# E77T.net
KiCad netlist of a schematic drawn in Altium Designer
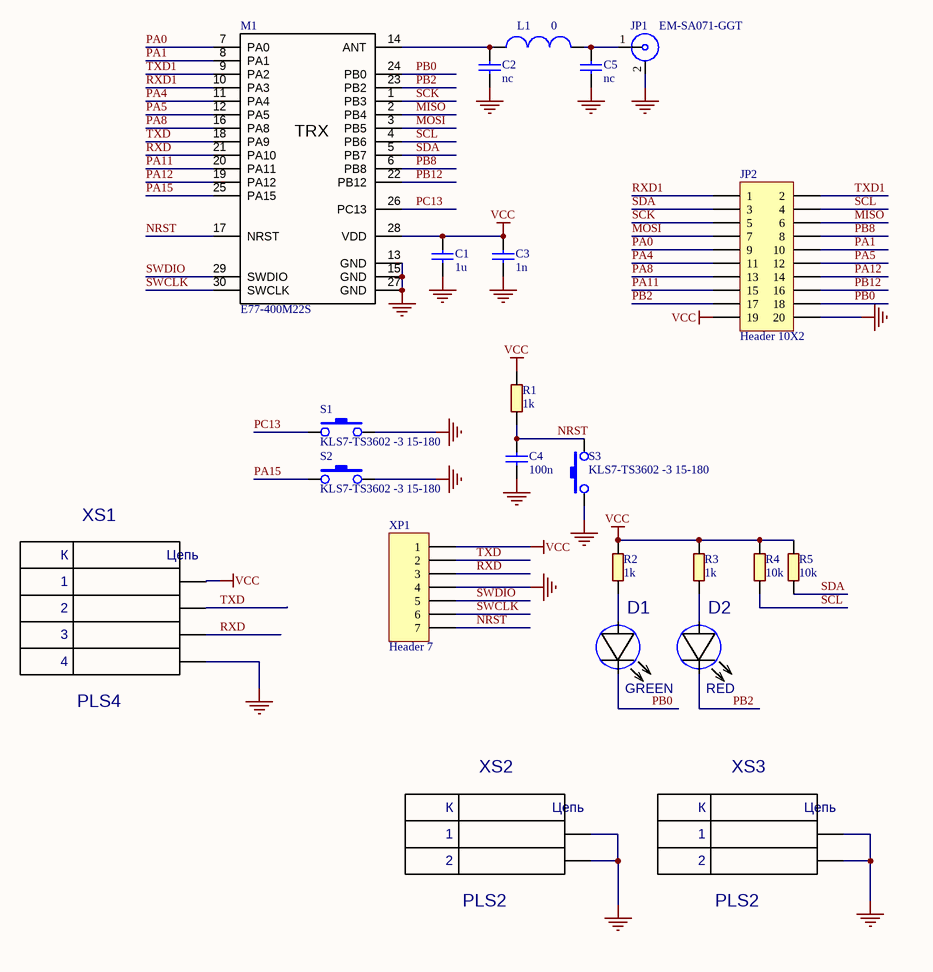
[diagram p0: E77T.SchDoc]

(export (version "E")
  (design (tool "Eeschema 10.0.6"))
  (components
    (comp (ref "C1")
      (value "1u")
      (footprint "C-0603")
      (fields (field (name "VOLTAGE") "50V"))
      (libsource (lib "Passive") (part "CAPN"))
    )
    (comp (ref "C2")
      (value "nc")
      (footprint "C-0603")
      (fields (field (name "VOLTAGE") "50V"))
      (libsource (lib "Passive") (part "CAPN"))
    )
    (comp (ref "C3")
      (value "1n")
      (footprint "C-0603")
      (fields (field (name "VOLTAGE") "50V"))
      (libsource (lib "Passive") (part "CAPN"))
    )
    (comp (ref "C4")
      (value "100n")
      (footprint "C-0603")
      (fields (field (name "VOLTAGE") "50V"))
      (libsource (lib "Passive") (part "CAPN"))
    )
    (comp (ref "C5")
      (value "nc")
      (footprint "C-0603")
      (fields (field (name "VOLTAGE") "50V"))
      (libsource (lib "Passive") (part "CAPN"))
    )
    (comp (ref "D1")
      (value "GREEN")
      (footprint "LED_3mm_RED")
      (fields (field (name "Comment") "LED3mm"))
      (libsource (lib "E2002") (part "LED3mm"))
    )
    (comp (ref "D2")
      (value "RED")
      (footprint "LED_3mm_RED")
      (fields (field (name "Comment") "LED3mm"))
      (libsource (lib "E2002") (part "LED3mm"))
    )
    (comp (ref "JP1")
      (value "EM-SA071-GGT")
      (footprint "SMA_F_EDGE")
      (description "SMA Female R/A PCB Mount")
      (libsource (lib "Connectors") (part "SMA"))
    )
    (comp (ref "JP2")
      (value "Header 10X2")
      (footprint "HDR2X10")
      (description "Header, 10-Pin, Dual row")
      (fields (field (name "PUBLISHER") "Altium Limited"))
      (libsource (lib "Miscellaneous Connectors") (part "Header 10X2"))
    )
    (comp (ref "L1") (value "0") (footprint "L-0603") (libsource (lib "Passive") (part "L")))
    (comp (ref "M1")
      (value "E77-400M22S")
      (footprint "E77XX-M22")
      (libsource (lib "zucker") (part "E77-400M22S"))
    )
    (comp (ref "R1") (value "1k") (footprint "R-0603") (libsource (lib "Passive") (part "RES")))
    (comp (ref "R2") (value "1k") (footprint "R-0603") (libsource (lib "Passive") (part "RES")))
    (comp (ref "R3") (value "1k") (footprint "R-0603") (libsource (lib "Passive") (part "RES")))
    (comp (ref "R4") (value "10k") (footprint "R-0603") (libsource (lib "Passive") (part "RES")))
    (comp (ref "R5") (value "10k") (footprint "R-0603") (libsource (lib "Passive") (part "RES")))
    (comp (ref "S1")
      (value "KLS7-TS3602 -3 15-180")
      (footprint "BUTT_MIN")
      (libsource (lib "Switches") (part "SW-1"))
    )
    (comp (ref "S2")
      (value "KLS7-TS3602 -3 15-180")
      (footprint "BUTT_MIN")
      (libsource (lib "Switches") (part "SW-1"))
    )
    (comp (ref "S3")
      (value "KLS7-TS3602 -3 15-180")
      (footprint "BUTT_MIN")
      (libsource (lib "Switches") (part "SW-1"))
    )
    (comp (ref "XP1")
      (value "Header 7")
      (footprint "PLS1-7R")
      (description "Header, 7-Pin")
      (fields (field (name "PUBLISHER") "Altium Limited"))
      (libsource (lib "Miscellaneous Connectors") (part "Header 7"))
    )
    (comp (ref "XS1") (value "PLS4") (footprint "PLS4 - 3D") (libsource (lib "E2002") (part "PLS4")))
    (comp (ref "XS2") (value "PLS2") (footprint "PLS2 - 3D") (libsource (lib "E2002") (part "PLS2")))
    (comp (ref "XS3") (value "PLS2") (footprint "PLS2 - 3D") (libsource (lib "E2002") (part "PLS2")))
  )
  (nets
    (net (code "1") (name "/MISO") (class "Default")
      (node (ref "JP2") (pin "6") (pinfunction "6_6") (pintype "passive"))
      (node (ref "M1") (pin "2") (pinfunction "PB4_2") (pintype "passive"))
    )
    (net (code "2") (name "/MOSI") (class "Default")
      (node (ref "JP2") (pin "7") (pinfunction "7_7") (pintype "passive"))
      (node (ref "M1") (pin "3") (pinfunction "PB5_3") (pintype "passive"))
    )
    (net (code "3") (name "/NRST") (class "Default")
      (node (ref "C4") (pin "1") (pinfunction "1_1") (pintype "passive"))
      (node (ref "M1") (pin "17") (pinfunction "NRST_17") (pintype "passive"))
      (node (ref "R1") (pin "1") (pinfunction "1_1") (pintype "passive"))
      (node (ref "S3") (pin "2") (pinfunction "2_2") (pintype "passive"))
      (node (ref "XP1") (pin "7") (pinfunction "7_7") (pintype "passive"))
    )
    (net (code "4") (name "/PA0") (class "Default")
      (node (ref "JP2") (pin "9") (pinfunction "9_9") (pintype "passive"))
      (node (ref "M1") (pin "7") (pinfunction "PA0_7") (pintype "passive"))
    )
    (net (code "5") (name "/PA1") (class "Default")
      (node (ref "JP2") (pin "10") (pinfunction "10_10") (pintype "passive"))
      (node (ref "M1") (pin "8") (pinfunction "PA1_8") (pintype "passive"))
    )
    (net (code "6") (name "/PA4") (class "Default")
      (node (ref "JP2") (pin "11") (pinfunction "11_11") (pintype "passive"))
      (node (ref "M1") (pin "11") (pinfunction "PA4_11") (pintype "passive"))
    )
    (net (code "7") (name "/PA5") (class "Default")
      (node (ref "JP2") (pin "12") (pinfunction "12_12") (pintype "passive"))
      (node (ref "M1") (pin "12") (pinfunction "PA5_12") (pintype "passive"))
    )
    (net (code "8") (name "/PA8") (class "Default")
      (node (ref "JP2") (pin "13") (pinfunction "13_13") (pintype "passive"))
      (node (ref "M1") (pin "16") (pinfunction "PA8_16") (pintype "passive"))
    )
    (net (code "9") (name "/PA11") (class "Default")
      (node (ref "JP2") (pin "15") (pinfunction "15_15") (pintype "passive"))
      (node (ref "M1") (pin "20") (pinfunction "PA11_20") (pintype "passive"))
    )
    (net (code "10") (name "/PA12") (class "Default")
      (node (ref "JP2") (pin "14") (pinfunction "14_14") (pintype "passive"))
      (node (ref "M1") (pin "19") (pinfunction "PA12_19") (pintype "passive"))
    )
    (net (code "11") (name "/PA15") (class "Default")
      (node (ref "M1") (pin "25") (pinfunction "PA15_25") (pintype "passive"))
      (node (ref "S2") (pin "1") (pinfunction "1_1") (pintype "passive"))
    )
    (net (code "12") (name "/PB0") (class "Default")
      (node (ref "D1") (pin "2") (pinfunction "2_2") (pintype "passive"))
      (node (ref "JP2") (pin "18") (pinfunction "18_18") (pintype "passive"))
      (node (ref "M1") (pin "24") (pinfunction "PB0_24") (pintype "passive"))
    )
    (net (code "13") (name "/PB2") (class "Default")
      (node (ref "D2") (pin "2") (pinfunction "2_2") (pintype "passive"))
      (node (ref "JP2") (pin "17") (pinfunction "17_17") (pintype "passive"))
      (node (ref "M1") (pin "23") (pinfunction "PB2_23") (pintype "passive"))
    )
    (net (code "14") (name "/PB8") (class "Default")
      (node (ref "JP2") (pin "8") (pinfunction "8_8") (pintype "passive"))
      (node (ref "M1") (pin "6") (pinfunction "PB8_6") (pintype "passive"))
    )
    (net (code "15") (name "/PB12") (class "Default")
      (node (ref "JP2") (pin "16") (pinfunction "16_16") (pintype "passive"))
      (node (ref "M1") (pin "22") (pinfunction "PB12_22") (pintype "passive"))
    )
    (net (code "16") (name "/PC13") (class "Default")
      (node (ref "M1") (pin "26") (pinfunction "PC13_26") (pintype "passive"))
      (node (ref "S1") (pin "1") (pinfunction "1_1") (pintype "passive"))
    )
    (net (code "17") (name "/RXD") (class "Default")
      (node (ref "M1") (pin "21") (pinfunction "PA10_21") (pintype "passive"))
      (node (ref "XP1") (pin "3") (pinfunction "3_3") (pintype "passive"))
      (node (ref "XS1") (pin "3") (pinfunction "3_3") (pintype "passive"))
    )
    (net (code "18") (name "/RXD1") (class "Default")
      (node (ref "JP2") (pin "1") (pinfunction "1_1") (pintype "passive"))
      (node (ref "M1") (pin "10") (pinfunction "PA3_10") (pintype "passive"))
    )
    (net (code "19") (name "/SCK") (class "Default")
      (node (ref "JP2") (pin "5") (pinfunction "5_5") (pintype "passive"))
      (node (ref "M1") (pin "1") (pinfunction "PB3_1") (pintype "passive"))
    )
    (net (code "20") (name "/SCL") (class "Default")
      (node (ref "JP2") (pin "4") (pinfunction "4_4") (pintype "passive"))
      (node (ref "M1") (pin "4") (pinfunction "PB6_4") (pintype "passive"))
      (node (ref "R4") (pin "1") (pinfunction "1_1") (pintype "passive"))
    )
    (net (code "21") (name "/SDA") (class "Default")
      (node (ref "JP2") (pin "3") (pinfunction "3_3") (pintype "passive"))
      (node (ref "M1") (pin "5") (pinfunction "PB7_5") (pintype "passive"))
      (node (ref "R5") (pin "1") (pinfunction "1_1") (pintype "passive"))
    )
    (net (code "22") (name "/SWCLK") (class "Default")
      (node (ref "M1") (pin "30") (pinfunction "SWCLK_30") (pintype "passive"))
      (node (ref "XP1") (pin "6") (pinfunction "6_6") (pintype "passive"))
    )
    (net (code "23") (name "/SWDIO") (class "Default")
      (node (ref "M1") (pin "29") (pinfunction "SWDIO_29") (pintype "passive"))
      (node (ref "XP1") (pin "5") (pinfunction "5_5") (pintype "passive"))
    )
    (net (code "24") (name "/TXD") (class "Default")
      (node (ref "M1") (pin "18") (pinfunction "PA9_18") (pintype "passive"))
      (node (ref "XP1") (pin "2") (pinfunction "2_2") (pintype "passive"))
      (node (ref "XS1") (pin "2") (pinfunction "2_2") (pintype "passive"))
    )
    (net (code "25") (name "/TXD1") (class "Default")
      (node (ref "JP2") (pin "2") (pinfunction "2_2") (pintype "passive"))
      (node (ref "M1") (pin "9") (pinfunction "PA2_9") (pintype "passive"))
    )
    (net (code "26") (name "GND") (class "Default")
      (node (ref "C1") (pin "2") (pinfunction "2_2") (pintype "passive"))
      (node (ref "C2") (pin "2") (pinfunction "2_2") (pintype "passive"))
      (node (ref "C3") (pin "2") (pinfunction "2_2") (pintype "passive"))
      (node (ref "C4") (pin "2") (pinfunction "2_2") (pintype "passive"))
      (node (ref "C5") (pin "2") (pinfunction "2_2") (pintype "passive"))
      (node (ref "JP1") (pin "2") (pinfunction "2_2") (pintype "passive"))
      (node (ref "JP2") (pin "20") (pinfunction "20_20") (pintype "passive"))
      (node (ref "M1") (pin "13") (pinfunction "GND_13") (pintype "passive"))
      (node (ref "M1") (pin "15") (pinfunction "GND_15") (pintype "passive"))
      (node (ref "M1") (pin "27") (pinfunction "GND_27") (pintype "passive"))
      (node (ref "S1") (pin "2") (pinfunction "2_2") (pintype "passive"))
      (node (ref "S2") (pin "2") (pinfunction "2_2") (pintype "passive"))
      (node (ref "S3") (pin "1") (pinfunction "1_1") (pintype "passive"))
      (node (ref "XP1") (pin "4") (pinfunction "4_4") (pintype "passive"))
      (node (ref "XS1") (pin "4") (pinfunction "4_4") (pintype "passive"))
      (node (ref "XS2") (pin "1") (pinfunction "1_1") (pintype "passive"))
      (node (ref "XS2") (pin "2") (pinfunction "2_2") (pintype "passive"))
      (node (ref "XS3") (pin "1") (pinfunction "1_1") (pintype "passive"))
      (node (ref "XS3") (pin "2") (pinfunction "2_2") (pintype "passive"))
    )
    (net (code "27") (name "Net-(C5-Pad1)") (class "Default")
      (node (ref "C5") (pin "1") (pinfunction "1_1") (pintype "passive"))
      (node (ref "JP1") (pin "1") (pinfunction "1_1") (pintype "passive"))
      (node (ref "L1") (pin "2") (pinfunction "2_2") (pintype "passive"))
    )
    (net (code "28") (name "Net-(D1-Pad1)") (class "Default")
      (node (ref "D1") (pin "1") (pinfunction "1_1") (pintype "passive"))
      (node (ref "R2") (pin "1") (pinfunction "1_1") (pintype "passive"))
    )
    (net (code "29") (name "Net-(D2-Pad1)") (class "Default")
      (node (ref "D2") (pin "1") (pinfunction "1_1") (pintype "passive"))
      (node (ref "R3") (pin "1") (pinfunction "1_1") (pintype "passive"))
    )
    (net (code "30") (name "Net-(M1-ANT)") (class "Default")
      (node (ref "C2") (pin "1") (pinfunction "1_1") (pintype "passive"))
      (node (ref "L1") (pin "1") (pinfunction "1_1") (pintype "passive"))
      (node (ref "M1") (pin "14") (pinfunction "ANT_14") (pintype "passive"))
    )
    (net (code "31") (name "VCC") (class "Default")
      (node (ref "C1") (pin "1") (pinfunction "1_1") (pintype "passive"))
      (node (ref "C3") (pin "1") (pinfunction "1_1") (pintype "passive"))
      (node (ref "JP2") (pin "19") (pinfunction "19_19") (pintype "passive"))
      (node (ref "M1") (pin "28") (pinfunction "VDD_28") (pintype "passive"))
      (node (ref "R1") (pin "2") (pinfunction "2_2") (pintype "passive"))
      (node (ref "R2") (pin "2") (pinfunction "2_2") (pintype "passive"))
      (node (ref "R3") (pin "2") (pinfunction "2_2") (pintype "passive"))
      (node (ref "R4") (pin "2") (pinfunction "2_2") (pintype "passive"))
      (node (ref "R5") (pin "2") (pinfunction "2_2") (pintype "passive"))
      (node (ref "XP1") (pin "1") (pinfunction "1_1") (pintype "passive"))
      (node (ref "XS1") (pin "1") (pinfunction "1_1") (pintype "passive"))
    )
  )
)
